# freezer_alarm-small.net
KiCad netlist of a schematic drawn in EAGLE
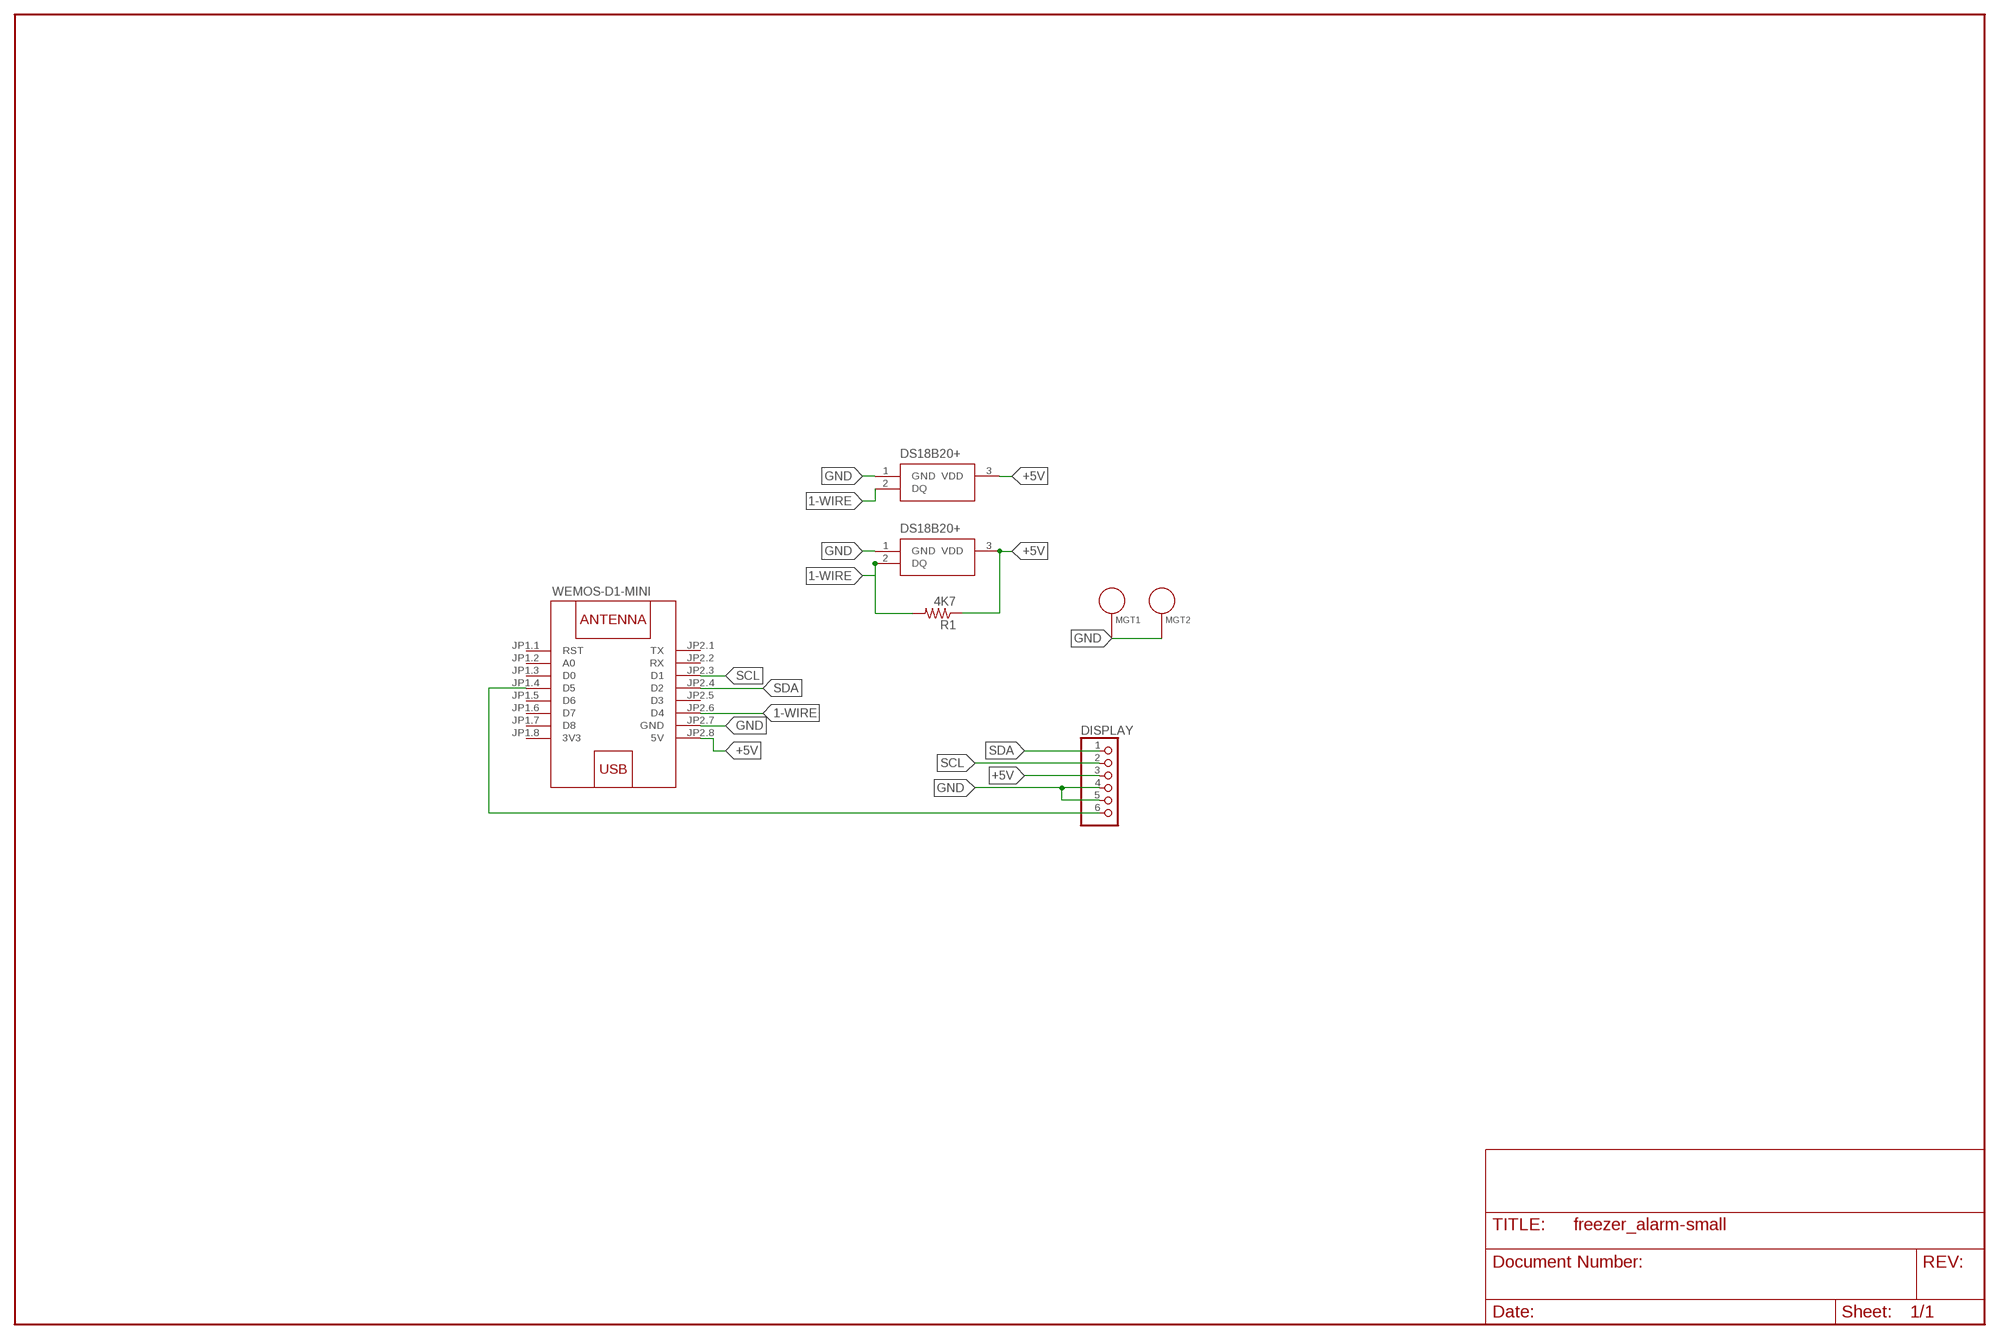
[diagram p0: schematic, sheet 1]

(export (version "E")
  (design (tool "Eeschema 10.0.6"))
  (components
    (comp (ref "DISPLAY")
      (value "PINHD-1X6")
      (footprint "eagle-import:1X06")
      (libsource (lib "eagle-import") (part "PINHD-1X6"))
    )
    (comp (ref "IC1")
      (value "DS18B20+")
      (footprint "eagle-import:TO-92")
      (fields (field (name "MOUSER_PART_NUMBER") "700-DS18B20+"))
      (libsource (lib "eagle-import") (part "DS18B20+"))
    )
    (comp (ref "IC2")
      (value "DS18B20+")
      (footprint "eagle-import:TO-92")
      (fields (field (name "MOUSER_PART_NUMBER") "700-DS18B20+"))
      (libsource (lib "eagle-import") (part "DS18B20+"))
    )
    (comp (ref "MGT1")
      (value "BEAGLEBONEBLACK_MOUNTING_HOLE")
      (footprint "eagle-import:BEAGLEBONEBLACK_MOUNTING_HOLE")
      (libsource (lib "eagle-import") (part "BEAGLEBONEBLACK_MOUNTING_HOLE"))
    )
    (comp (ref "MGT2")
      (value "BEAGLEBONEBLACK_MOUNTING_HOLE")
      (footprint "eagle-import:BEAGLEBONEBLACK_MOUNTING_HOLE")
      (libsource (lib "eagle-import") (part "BEAGLEBONEBLACK_MOUNTING_HOLE"))
    )
    (comp (ref "R1")
      (value "4K7")
      (footprint "eagle-import:0207_10")
      (libsource (lib "eagle-import") (part "R-US_0207/10"))
    )
    (comp (ref "W1")
      (value "WEMOS-D1-MINI")
      (footprint "eagle-import:WEMOS-D1-MINI")
      (libsource (lib "eagle-import") (part "WEMOS-D1-MINI"))
    )
  )
  (nets
    (net (code "1") (name "+5V") (class "Default")
      (node (ref "DISPLAY") (pin "3") (pinfunction "3_3") (pintype "passive"))
      (node (ref "IC1") (pin "3") (pinfunction "VDD_3") (pintype "power_in"))
      (node (ref "IC2") (pin "3") (pinfunction "VDD_3") (pintype "power_in"))
      (node (ref "R1") (pin "1") (pinfunction "1_1") (pintype "passive"))
      (node (ref "W1") (pin "JP2.8") (pinfunction "5V_JP2.8") (pintype "power_in"))
    )
    (net (code "2") (name "/3V3") (class "Default")
      (node (ref "W1") (pin "JP1.8") (pinfunction "3V3_JP1.8") (pintype "power_in"))
    )
    (net (code "3") (name "1-WIRE") (class "Default")
      (node (ref "IC1") (pin "2") (pinfunction "DQ_2") (pintype "bidirectional"))
      (node (ref "IC2") (pin "2") (pinfunction "DQ_2") (pintype "bidirectional"))
      (node (ref "R1") (pin "2") (pinfunction "2_2") (pintype "passive"))
      (node (ref "W1") (pin "JP2.6") (pinfunction "D4_JP2.6") (pintype "bidirectional"))
    )
    (net (code "4") (name "GND") (class "Default")
      (node (ref "DISPLAY") (pin "4") (pinfunction "4_4") (pintype "passive"))
      (node (ref "DISPLAY") (pin "5") (pinfunction "5_5") (pintype "passive"))
      (node (ref "IC1") (pin "1") (pinfunction "GND_1") (pintype "power_in"))
      (node (ref "IC2") (pin "1") (pinfunction "GND_1") (pintype "power_in"))
      (node (ref "W1") (pin "JP2.7") (pinfunction "GND_JP2.7") (pintype "power_in"))
    )
    (net (code "5") (name "Net-(MGT1-PadP$1)") (class "Default")
      (node (ref "MGT1") (pin "P$1") (pinfunction "P$1_P$1") (pintype "bidirectional"))
      (node (ref "MGT2") (pin "P$1") (pinfunction "P$1_P$1") (pintype "bidirectional"))
    )
    (net (code "6") (name "Net-(W1-D5)") (class "Default")
      (node (ref "DISPLAY") (pin "6") (pinfunction "6_6") (pintype "passive"))
      (node (ref "W1") (pin "JP1.4") (pinfunction "D5_JP1.4") (pintype "bidirectional"))
    )
    (net (code "7") (name "SCL") (class "Default")
      (node (ref "DISPLAY") (pin "2") (pinfunction "2_2") (pintype "passive"))
      (node (ref "W1") (pin "JP2.3") (pinfunction "D1_JP2.3") (pintype "bidirectional"))
    )
    (net (code "8") (name "SDA") (class "Default")
      (node (ref "DISPLAY") (pin "1") (pinfunction "1_1") (pintype "passive"))
      (node (ref "W1") (pin "JP2.4") (pinfunction "D2_JP2.4") (pintype "bidirectional"))
    )
    (net (code "9") (name "unconnected-(W1-A0-PadJP1.2)") (class "Default")
      (node (ref "W1") (pin "JP1.2") (pinfunction "A0_JP1.2") (pintype "bidirectional"))
    )
    (net (code "10") (name "unconnected-(W1-D0-PadJP1.3)") (class "Default")
      (node (ref "W1") (pin "JP1.3") (pinfunction "D0_JP1.3") (pintype "bidirectional"))
    )
    (net (code "11") (name "unconnected-(W1-D3-PadJP2.5)") (class "Default")
      (node (ref "W1") (pin "JP2.5") (pinfunction "D3_JP2.5") (pintype "bidirectional"))
    )
    (net (code "12") (name "unconnected-(W1-D6-PadJP1.5)") (class "Default")
      (node (ref "W1") (pin "JP1.5") (pinfunction "D6_JP1.5") (pintype "bidirectional"))
    )
    (net (code "13") (name "unconnected-(W1-D7-PadJP1.6)") (class "Default")
      (node (ref "W1") (pin "JP1.6") (pinfunction "D7_JP1.6") (pintype "bidirectional"))
    )
    (net (code "14") (name "unconnected-(W1-D8-PadJP1.7)") (class "Default")
      (node (ref "W1") (pin "JP1.7") (pinfunction "D8_JP1.7") (pintype "bidirectional"))
    )
    (net (code "15") (name "unconnected-(W1-RST-PadJP1.1)") (class "Default")
      (node (ref "W1") (pin "JP1.1") (pinfunction "RST_JP1.1") (pintype "bidirectional"))
    )
    (net (code "16") (name "unconnected-(W1-RX-PadJP2.2)") (class "Default")
      (node (ref "W1") (pin "JP2.2") (pinfunction "RX_JP2.2") (pintype "bidirectional"))
    )
    (net (code "17") (name "unconnected-(W1-TX-PadJP2.1)") (class "Default")
      (node (ref "W1") (pin "JP2.1") (pinfunction "TX_JP2.1") (pintype "bidirectional"))
    )
  )
)
